# lights_node.net
KiCad netlist of a schematic drawn in EAGLE
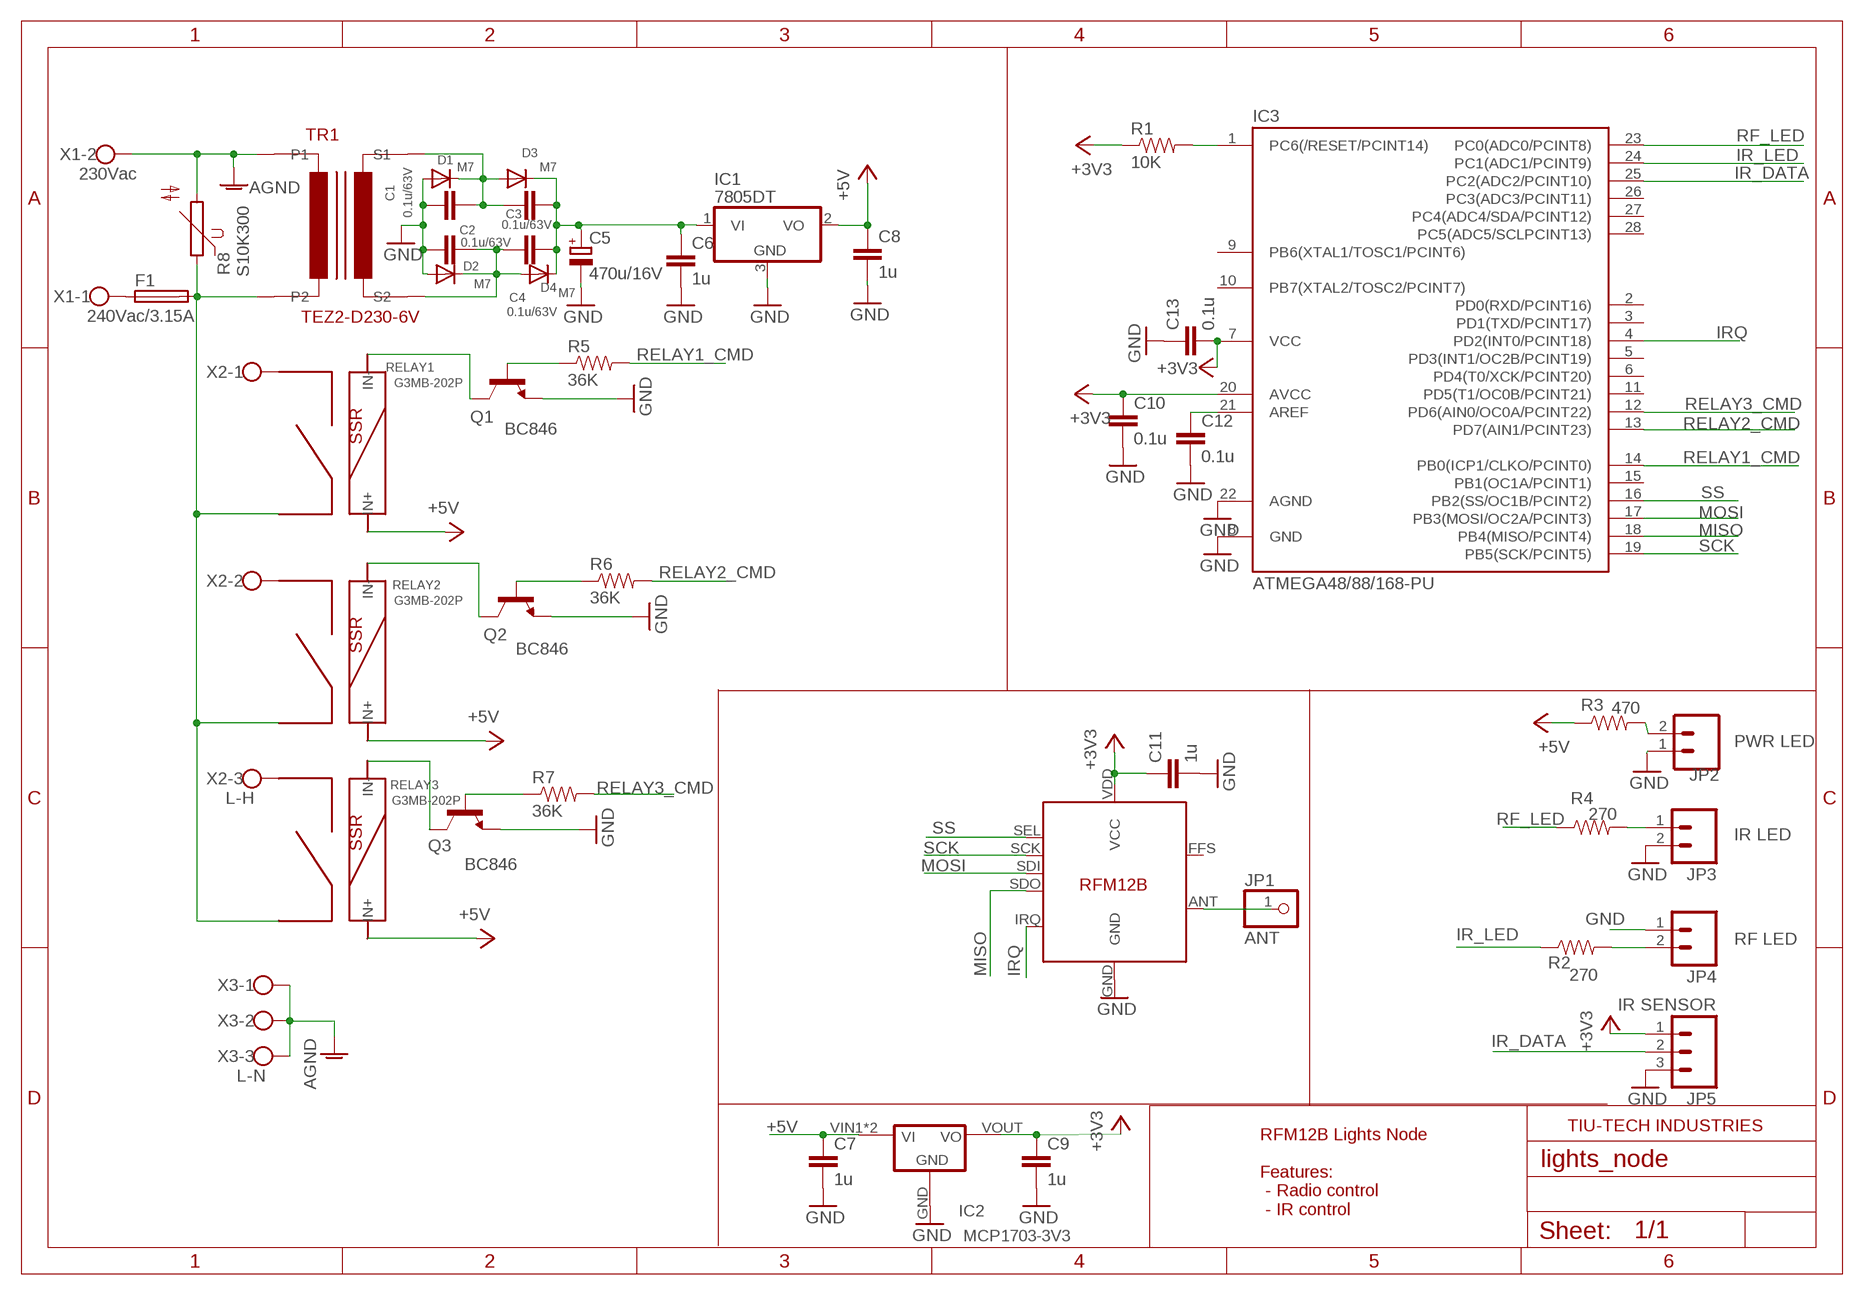
[diagram p0: schematic, sheet 1]

(export (version "E")
  (design (tool "Eeschema 10.0.6"))
  (components
    (comp (ref "C1")
      (value "0.1u/63V")
      (footprint "eagle-import:0805")
      (libsource (lib "eagle-import") (part "CAP0805"))
    )
    (comp (ref "C2")
      (value "0.1u/63V")
      (footprint "eagle-import:0805")
      (libsource (lib "eagle-import") (part "CAP0805"))
    )
    (comp (ref "C3")
      (value "0.1u/63V")
      (footprint "eagle-import:0805")
      (libsource (lib "eagle-import") (part "CAP0805"))
    )
    (comp (ref "C4")
      (value "0.1u/63V")
      (footprint "eagle-import:0805")
      (libsource (lib "eagle-import") (part "CAP0805"))
    )
    (comp (ref "C5")
      (value "470u/16V")
      (footprint "eagle-import:E2,5-7")
      (libsource (lib "eagle-import") (part "CPOL-EUE2.5-7"))
    )
    (comp (ref "C6")
      (value "1u")
      (footprint "eagle-import:0805")
      (libsource (lib "eagle-import") (part "CAP0805"))
    )
    (comp (ref "C7")
      (value "1u")
      (footprint "eagle-import:0805")
      (libsource (lib "eagle-import") (part "CAP0805"))
    )
    (comp (ref "C8")
      (value "1u")
      (footprint "eagle-import:0805")
      (libsource (lib "eagle-import") (part "CAP0805"))
    )
    (comp (ref "C9")
      (value "1u")
      (footprint "eagle-import:0805")
      (libsource (lib "eagle-import") (part "CAP0805"))
    )
    (comp (ref "C10")
      (value "0.1u")
      (footprint "eagle-import:0805")
      (libsource (lib "eagle-import") (part "CAP0805"))
    )
    (comp (ref "C11")
      (value "1u")
      (footprint "eagle-import:0805")
      (libsource (lib "eagle-import") (part "CAP0805"))
    )
    (comp (ref "C12")
      (value "0.1u")
      (footprint "eagle-import:0805")
      (libsource (lib "eagle-import") (part "CAP0805"))
    )
    (comp (ref "C13")
      (value "0.1u")
      (footprint "eagle-import:0805")
      (libsource (lib "eagle-import") (part "CAP0805"))
    )
    (comp (ref "D1")
      (value "M7")
      (footprint "eagle-import:DO-214AC")
      (libsource (lib "eagle-import") (part "DIODE-DO-214AC"))
    )
    (comp (ref "D2")
      (value "M7")
      (footprint "eagle-import:DO-214AC")
      (libsource (lib "eagle-import") (part "DIODE-DO-214AC"))
    )
    (comp (ref "D3")
      (value "M7")
      (footprint "eagle-import:DO-214AC")
      (libsource (lib "eagle-import") (part "DIODE-DO-214AC"))
    )
    (comp (ref "D4")
      (value "M7")
      (footprint "eagle-import:DO-214AC")
      (libsource (lib "eagle-import") (part "DIODE-DO-214AC"))
    )
    (comp (ref "F1")
      (value "240Vac/3.15A")
      (footprint "eagle-import:PICOFUSE")
      (libsource (lib "eagle-import") (part "PICOFUSE"))
    )
    (comp (ref "IC1")
      (value "7805DT")
      (footprint "eagle-import:TO252")
      (libsource (lib "eagle-import") (part "78DT05"))
    )
    (comp (ref "IC2")
      (value "MCP1703-3V3")
      (footprint "eagle-import:MCP1703-SOT89")
      (libsource (lib "eagle-import") (part "MCP1703-SOT89"))
    )
    (comp (ref "IC3")
      (value "ATMEGA48/88/168-PU")
      (footprint "eagle-import:DIL28-3")
      (libsource (lib "eagle-import") (part "ATMEGA48/88/168-PU"))
    )
    (comp (ref "JP1")
      (value "ANT")
      (footprint "eagle-import:1X01")
      (libsource (lib "eagle-import") (part "PINHD-1X1"))
    )
    (comp (ref "JP2")
      (value "M02PTH")
      (footprint "eagle-import:1X02")
      (libsource (lib "eagle-import") (part "M02PTH"))
    )
    (comp (ref "JP3")
      (value "M02PTH")
      (footprint "eagle-import:1X02")
      (libsource (lib "eagle-import") (part "M02PTH"))
    )
    (comp (ref "JP4")
      (value "M02PTH")
      (footprint "eagle-import:1X02")
      (libsource (lib "eagle-import") (part "M02PTH"))
    )
    (comp (ref "JP5")
      (value "IR SENSOR")
      (footprint "eagle-import:1X03")
      (libsource (lib "eagle-import") (part "M03PTH"))
    )
    (comp (ref "Q1")
      (value "BC846")
      (footprint "eagle-import:SOT23-BEC")
      (libsource (lib "eagle-import") (part "-NPN-SOT23-BECBC847C"))
    )
    (comp (ref "Q2")
      (value "BC846")
      (footprint "eagle-import:SOT23-BEC")
      (libsource (lib "eagle-import") (part "-NPN-SOT23-BECBC847C"))
    )
    (comp (ref "Q3")
      (value "BC846")
      (footprint "eagle-import:SOT23-BEC")
      (libsource (lib "eagle-import") (part "-NPN-SOT23-BECBC847C"))
    )
    (comp (ref "R1")
      (value "10K")
      (footprint "eagle-import:0805")
      (libsource (lib "eagle-import") (part "RESISTOR0805-RES"))
    )
    (comp (ref "R2")
      (value "270")
      (footprint "eagle-import:0805")
      (libsource (lib "eagle-import") (part "RESISTOR0805-RES"))
    )
    (comp (ref "R3")
      (value "470")
      (footprint "eagle-import:0805")
      (libsource (lib "eagle-import") (part "RESISTOR0805-RES"))
    )
    (comp (ref "R4")
      (value "270")
      (footprint "eagle-import:0805")
      (libsource (lib "eagle-import") (part "RESISTOR0805-RES"))
    )
    (comp (ref "R5")
      (value "36K")
      (footprint "eagle-import:0805")
      (libsource (lib "eagle-import") (part "SparkFun-Resistors_RESISTOR0805-RES"))
    )
    (comp (ref "R6")
      (value "36K")
      (footprint "eagle-import:0805")
      (libsource (lib "eagle-import") (part "SparkFun-Resistors_RESISTOR0805-RES"))
    )
    (comp (ref "R7")
      (value "36K")
      (footprint "eagle-import:0805")
      (libsource (lib "eagle-import") (part "SparkFun-Resistors_RESISTOR0805-RES"))
    )
    (comp (ref "R8")
      (value "S10K300")
      (footprint "eagle-import:S10K300")
      (libsource (lib "eagle-import") (part "S10K300"))
    )
    (comp (ref "RELAY1")
      (value "G3MB-202P")
      (footprint "eagle-import:G3MB-202P")
      (libsource (lib "eagle-import") (part "G3MB-202P"))
    )
    (comp (ref "RELAY2")
      (value "G3MB-202P")
      (footprint "eagle-import:G3MB-202P")
      (libsource (lib "eagle-import") (part "G3MB-202P"))
    )
    (comp (ref "RELAY3")
      (value "G3MB-202P")
      (footprint "eagle-import:G3MB-202P")
      (libsource (lib "eagle-import") (part "G3MB-202P"))
    )
    (comp (ref "RFM1")
      (value "RFM12B")
      (footprint "eagle-import:RFM12B")
      (libsource (lib "eagle-import") (part "RFM12B"))
    )
    (comp (ref "TR1")
      (value "TEZ2-D230-6V")
      (footprint "eagle-import:TEZ1.5-PKG")
      (libsource (lib "eagle-import") (part "TEZ1.5-D230-6V"))
    )
    (comp (ref "X1")
      (value "230Vac")
      (footprint "eagle-import:W237-102")
      (fields (field (name "MPN") "237-102"))
      (libsource (lib "eagle-import") (part "W237-102"))
    )
    (comp (ref "X2")
      (value "L-H")
      (footprint "eagle-import:W237-103")
      (fields (field (name "MPN") "237-103"))
      (libsource (lib "eagle-import") (part "W237-103"))
    )
    (comp (ref "X3")
      (value "L-N")
      (footprint "eagle-import:W237-103")
      (fields (field (name "MPN") "237-103"))
      (libsource (lib "eagle-import") (part "W237-103"))
    )
  )
  (nets
    (net (code "1") (name "+3V3") (class "Default")
      (node (ref "C10") (pin "1") (pinfunction "1_1") (pintype "passive"))
      (node (ref "C11") (pin "1") (pinfunction "1_1") (pintype "passive"))
      (node (ref "C13") (pin "2") (pinfunction "2_2") (pintype "passive"))
      (node (ref "C9") (pin "1") (pinfunction "1_1") (pintype "passive"))
      (node (ref "IC2") (pin "VOUT") (pinfunction "VO_VOUT") (pintype "passive"))
      (node (ref "IC3") (pin "20") (pinfunction "AVCC_20") (pintype "passive"))
      (node (ref "IC3") (pin "7") (pinfunction "VCC_7") (pintype "power_in"))
      (node (ref "JP5") (pin "1") (pinfunction "1_1") (pintype "passive"))
      (node (ref "R1") (pin "1") (pinfunction "1_1") (pintype "passive"))
      (node (ref "RFM1") (pin "VDD") (pinfunction "VCC_VDD") (pintype "power_in"))
    )
    (net (code "2") (name "+5V") (class "Default")
      (node (ref "C7") (pin "1") (pinfunction "1_1") (pintype "passive"))
      (node (ref "C8") (pin "1") (pinfunction "1_1") (pintype "passive"))
      (node (ref "IC1") (pin "2") (pinfunction "VO_2") (pintype "passive"))
      (node (ref "IC2") (pin "VIN1") (pinfunction "VI_VIN1") (pintype "power_in"))
      (node (ref "IC2") (pin "VIN2") (pinfunction "VI_VIN2") (pintype "power_in"))
      (node (ref "R3") (pin "1") (pinfunction "1_1") (pintype "passive"))
      (node (ref "RELAY1") (pin "IN+") (pinfunction "IN+_IN+") (pintype "bidirectional"))
      (node (ref "RELAY2") (pin "IN+") (pinfunction "IN+_IN+") (pintype "bidirectional"))
      (node (ref "RELAY3") (pin "IN+") (pinfunction "IN+_IN+") (pintype "bidirectional"))
    )
    (net (code "3") (name "/IRQ") (class "Default")
      (node (ref "IC3") (pin "4") (pinfunction "PD2(INT0/PCINT18)_4") (pintype "bidirectional"))
      (node (ref "RFM1") (pin "IRQ") (pinfunction "IRQ_IRQ") (pintype "open_collector"))
    )
    (net (code "4") (name "/IR_DATA") (class "Default")
      (node (ref "IC3") (pin "25") (pinfunction "PC2(ADC2/PCINT10)_25") (pintype "bidirectional"))
      (node (ref "JP5") (pin "2") (pinfunction "2_2") (pintype "passive"))
    )
    (net (code "5") (name "/IR_LED") (class "Default")
      (node (ref "IC3") (pin "24") (pinfunction "PC1(ADC1/PCINT9)_24") (pintype "bidirectional"))
      (node (ref "R2") (pin "1") (pinfunction "1_1") (pintype "passive"))
    )
    (net (code "6") (name "/MISO") (class "Default")
      (node (ref "IC3") (pin "18") (pinfunction "PB4(MISO/PCINT4)_18") (pintype "bidirectional"))
      (node (ref "RFM1") (pin "SDO") (pinfunction "SDO_SDO") (pintype "output"))
    )
    (net (code "7") (name "/MOSI") (class "Default")
      (node (ref "IC3") (pin "17") (pinfunction "PB3(MOSI/OC2A/PCINT3)_17") (pintype "bidirectional"))
      (node (ref "RFM1") (pin "SDI") (pinfunction "SDI_SDI") (pintype "input"))
    )
    (net (code "8") (name "/RELAY1_CMD") (class "Default")
      (node (ref "IC3") (pin "14") (pinfunction "PB0(ICP1/CLKO/PCINT0)_14") (pintype "bidirectional"))
      (node (ref "R5") (pin "2") (pinfunction "2_2") (pintype "passive"))
    )
    (net (code "9") (name "/RELAY2_CMD") (class "Default")
      (node (ref "IC3") (pin "13") (pinfunction "PD7(AIN1/PCINT23)_13") (pintype "bidirectional"))
      (node (ref "R6") (pin "2") (pinfunction "2_2") (pintype "passive"))
    )
    (net (code "10") (name "/RELAY3_CMD") (class "Default")
      (node (ref "IC3") (pin "12") (pinfunction "PD6(AIN0/OC0A/PCINT22)_12") (pintype "bidirectional"))
      (node (ref "R7") (pin "2") (pinfunction "2_2") (pintype "passive"))
    )
    (net (code "11") (name "/RF_LED") (class "Default")
      (node (ref "IC3") (pin "23") (pinfunction "PC0(ADC0/PCINT8)_23") (pintype "bidirectional"))
      (node (ref "R4") (pin "1") (pinfunction "1_1") (pintype "passive"))
    )
    (net (code "12") (name "/SCK") (class "Default")
      (node (ref "IC3") (pin "19") (pinfunction "PB5(SCK/PCINT5)_19") (pintype "bidirectional"))
      (node (ref "RFM1") (pin "SCK") (pinfunction "SCK_SCK") (pintype "input"))
    )
    (net (code "13") (name "/SS") (class "Default")
      (node (ref "IC3") (pin "16") (pinfunction "PB2(SS/OC1B/PCINT2)_16") (pintype "bidirectional"))
      (node (ref "RFM1") (pin "SEL") (pinfunction "SEL_SEL") (pintype "input"))
    )
    (net (code "14") (name "AGND") (class "Default")
      (node (ref "R8") (pin "2") (pinfunction "2_2") (pintype "passive"))
      (node (ref "TR1") (pin "P1") (pinfunction "P1_P1") (pintype "bidirectional"))
      (node (ref "X1") (pin "2") (pinfunction "KL_2") (pintype "passive"))
      (node (ref "X3") (pin "1") (pinfunction "KL_1") (pintype "passive"))
      (node (ref "X3") (pin "2") (pinfunction "KL_2") (pintype "passive"))
      (node (ref "X3") (pin "3") (pinfunction "KL_3") (pintype "passive"))
    )
    (net (code "15") (name "GND") (class "Default")
      (node (ref "C1") (pin "1") (pinfunction "1_1") (pintype "passive"))
      (node (ref "C10") (pin "2") (pinfunction "2_2") (pintype "passive"))
      (node (ref "C11") (pin "2") (pinfunction "2_2") (pintype "passive"))
      (node (ref "C12") (pin "2") (pinfunction "2_2") (pintype "passive"))
      (node (ref "C13") (pin "1") (pinfunction "1_1") (pintype "passive"))
      (node (ref "C2") (pin "1") (pinfunction "1_1") (pintype "passive"))
      (node (ref "C5") (pin "-") (pinfunction "-_-") (pintype "passive"))
      (node (ref "C6") (pin "2") (pinfunction "2_2") (pintype "passive"))
      (node (ref "C7") (pin "2") (pinfunction "2_2") (pintype "passive"))
      (node (ref "C8") (pin "2") (pinfunction "2_2") (pintype "passive"))
      (node (ref "C9") (pin "2") (pinfunction "2_2") (pintype "passive"))
      (node (ref "D1") (pin "A") (pinfunction "A_A") (pintype "passive"))
      (node (ref "D2") (pin "A") (pinfunction "A_A") (pintype "passive"))
      (node (ref "IC1") (pin "3") (pinfunction "GND_3") (pintype "passive"))
      (node (ref "IC2") (pin "GND") (pinfunction "GND_GND") (pintype "power_in"))
      (node (ref "IC3") (pin "22") (pinfunction "AGND_22") (pintype "power_in"))
      (node (ref "IC3") (pin "8") (pinfunction "GND_8") (pintype "power_in"))
      (node (ref "JP2") (pin "1") (pinfunction "1_1") (pintype "passive"))
      (node (ref "JP3") (pin "2") (pinfunction "2_2") (pintype "passive"))
      (node (ref "JP4") (pin "1") (pinfunction "1_1") (pintype "passive"))
      (node (ref "JP5") (pin "3") (pinfunction "3_3") (pintype "passive"))
      (node (ref "Q1") (pin "E") (pinfunction "E_E") (pintype "passive"))
      (node (ref "Q2") (pin "E") (pinfunction "E_E") (pintype "passive"))
      (node (ref "Q3") (pin "E") (pinfunction "E_E") (pintype "passive"))
      (node (ref "RFM1") (pin "GND") (pinfunction "GND_GND") (pintype "power_in"))
    )
    (net (code "16") (name "Net-(IC1-VI)") (class "Default")
      (node (ref "C3") (pin "2") (pinfunction "2_2") (pintype "passive"))
      (node (ref "C4") (pin "2") (pinfunction "2_2") (pintype "passive"))
      (node (ref "C5") (pin "+") (pinfunction "+_+") (pintype "passive"))
      (node (ref "C6") (pin "1") (pinfunction "1_1") (pintype "passive"))
      (node (ref "D3") (pin "C") (pinfunction "C_C") (pintype "passive"))
      (node (ref "D4") (pin "C") (pinfunction "C_C") (pintype "passive"))
      (node (ref "IC1") (pin "1") (pinfunction "VI_1") (pintype "input"))
    )
    (net (code "17") (name "Net-(IC3-AREF)") (class "Default")
      (node (ref "C12") (pin "1") (pinfunction "1_1") (pintype "passive"))
      (node (ref "IC3") (pin "21") (pinfunction "AREF_21") (pintype "passive"))
    )
    (net (code "18") (name "Net-(IC3-PC6({slash}RESET{slash}PCINT14))") (class "Default")
      (node (ref "IC3") (pin "1") (pinfunction "PC6(/RESET/PCINT14)_1") (pintype "bidirectional"))
      (node (ref "R1") (pin "2") (pinfunction "2_2") (pintype "passive"))
    )
    (net (code "19") (name "Net-(JP1-Pad1)") (class "Default")
      (node (ref "JP1") (pin "1") (pinfunction "1_1") (pintype "passive"))
      (node (ref "RFM1") (pin "ANT") (pinfunction "ANT_ANT") (pintype "passive"))
    )
    (net (code "20") (name "Net-(JP2-Pad2)") (class "Default")
      (node (ref "JP2") (pin "2") (pinfunction "2_2") (pintype "passive"))
      (node (ref "R3") (pin "2") (pinfunction "2_2") (pintype "passive"))
    )
    (net (code "21") (name "Net-(JP3-Pad1)") (class "Default")
      (node (ref "JP3") (pin "1") (pinfunction "1_1") (pintype "passive"))
      (node (ref "R4") (pin "2") (pinfunction "2_2") (pintype "passive"))
    )
    (net (code "22") (name "Net-(JP4-Pad2)") (class "Default")
      (node (ref "JP4") (pin "2") (pinfunction "2_2") (pintype "passive"))
      (node (ref "R2") (pin "2") (pinfunction "2_2") (pintype "passive"))
    )
    (net (code "23") (name "Net-(Q1-PadB)") (class "Default")
      (node (ref "Q1") (pin "B") (pinfunction "B_B") (pintype "passive"))
      (node (ref "R5") (pin "1") (pinfunction "1_1") (pintype "passive"))
    )
    (net (code "24") (name "Net-(Q1-PadC)") (class "Default")
      (node (ref "Q1") (pin "C") (pinfunction "C_C") (pintype "passive"))
      (node (ref "RELAY1") (pin "IN-") (pinfunction "IN-_IN-") (pintype "bidirectional"))
    )
    (net (code "25") (name "Net-(Q2-PadB)") (class "Default")
      (node (ref "Q2") (pin "B") (pinfunction "B_B") (pintype "passive"))
      (node (ref "R6") (pin "1") (pinfunction "1_1") (pintype "passive"))
    )
    (net (code "26") (name "Net-(Q2-PadC)") (class "Default")
      (node (ref "Q2") (pin "C") (pinfunction "C_C") (pintype "passive"))
      (node (ref "RELAY2") (pin "IN-") (pinfunction "IN-_IN-") (pintype "bidirectional"))
    )
    (net (code "27") (name "Net-(Q3-PadB)") (class "Default")
      (node (ref "Q3") (pin "B") (pinfunction "B_B") (pintype "passive"))
      (node (ref "R7") (pin "1") (pinfunction "1_1") (pintype "passive"))
    )
    (net (code "28") (name "Net-(Q3-PadC)") (class "Default")
      (node (ref "Q3") (pin "C") (pinfunction "C_C") (pintype "passive"))
      (node (ref "RELAY3") (pin "IN-") (pinfunction "IN-_IN-") (pintype "bidirectional"))
    )
    (net (code "29") (name "Net-(TR1-P2)") (class "Default")
      (node (ref "F1") (pin "2") (pinfunction "2_2") (pintype "passive"))
      (node (ref "R8") (pin "1") (pinfunction "1_1") (pintype "passive"))
      (node (ref "RELAY1") (pin "K1") (pinfunction "K1_K1") (pintype "bidirectional"))
      (node (ref "RELAY2") (pin "K1") (pinfunction "K1_K1") (pintype "bidirectional"))
      (node (ref "RELAY3") (pin "K1") (pinfunction "K1_K1") (pintype "bidirectional"))
      (node (ref "TR1") (pin "P5") (pinfunction "P2_P5") (pintype "bidirectional"))
    )
    (net (code "30") (name "Net-(TR1-S1)") (class "Default")
      (node (ref "C1") (pin "2") (pinfunction "2_2") (pintype "passive"))
      (node (ref "C3") (pin "1") (pinfunction "1_1") (pintype "passive"))
      (node (ref "D1") (pin "C") (pinfunction "C_C") (pintype "passive"))
      (node (ref "D3") (pin "A") (pinfunction "A_A") (pintype "passive"))
      (node (ref "TR1") (pin "S7") (pinfunction "S1_S7") (pintype "bidirectional"))
    )
    (net (code "31") (name "Net-(TR1-S2)") (class "Default")
      (node (ref "C2") (pin "2") (pinfunction "2_2") (pintype "passive"))
      (node (ref "C4") (pin "1") (pinfunction "1_1") (pintype "passive"))
      (node (ref "D2") (pin "C") (pinfunction "C_C") (pintype "passive"))
      (node (ref "D4") (pin "A") (pinfunction "A_A") (pintype "passive"))
      (node (ref "TR1") (pin "S9") (pinfunction "S2_S9") (pintype "bidirectional"))
    )
    (net (code "32") (name "Net-(X1A-KL)") (class "Default")
      (node (ref "F1") (pin "1") (pinfunction "1_1") (pintype "passive"))
      (node (ref "X1") (pin "1") (pinfunction "KL_1") (pintype "passive"))
    )
    (net (code "33") (name "Net-(X2A-KL)") (class "Default")
      (node (ref "RELAY1") (pin "K2") (pinfunction "K2_K2") (pintype "bidirectional"))
      (node (ref "X2") (pin "1") (pinfunction "KL_1") (pintype "passive"))
    )
    (net (code "34") (name "Net-(X2B-KL)") (class "Default")
      (node (ref "RELAY2") (pin "K2") (pinfunction "K2_K2") (pintype "bidirectional"))
      (node (ref "X2") (pin "2") (pinfunction "KL_2") (pintype "passive"))
    )
    (net (code "35") (name "Net-(X2C-KL)") (class "Default")
      (node (ref "RELAY3") (pin "K2") (pinfunction "K2_K2") (pintype "bidirectional"))
      (node (ref "X2") (pin "3") (pinfunction "KL_3") (pintype "passive"))
    )
    (net (code "36") (name "unconnected-(IC3-PB1(OC1A{slash}PCINT1)-Pad15)") (class "Default")
      (node (ref "IC3") (pin "15") (pinfunction "PB1(OC1A/PCINT1)_15") (pintype "bidirectional"))
    )
    (net (code "37") (name "unconnected-(IC3-PB6(XTAL1{slash}TOSC1{slash}PCINT6)-Pad9)") (class "Default")
      (node (ref "IC3") (pin "9") (pinfunction "PB6(XTAL1/TOSC1/PCINT6)_9") (pintype "bidirectional"))
    )
    (net (code "38") (name "unconnected-(IC3-PB7(XTAL2{slash}TOSC2{slash}PCINT7)-Pad10)") (class "Default")
      (node (ref "IC3") (pin "10") (pinfunction "PB7(XTAL2/TOSC2/PCINT7)_10") (pintype "bidirectional"))
    )
    (net (code "39") (name "unconnected-(IC3-PC3(ADC3{slash}PCINT11)-Pad26)") (class "Default")
      (node (ref "IC3") (pin "26") (pinfunction "PC3(ADC3/PCINT11)_26") (pintype "bidirectional"))
    )
    (net (code "40") (name "unconnected-(IC3-PC4(ADC4{slash}SDA{slash}PCINT12)-Pad27)") (class "Default")
      (node (ref "IC3") (pin "27") (pinfunction "PC4(ADC4/SDA/PCINT12)_27") (pintype "bidirectional"))
    )
    (net (code "41") (name "unconnected-(IC3-PC5(ADC5{slash}SCLPCINT13)-Pad28)") (class "Default")
      (node (ref "IC3") (pin "28") (pinfunction "PC5(ADC5/SCLPCINT13)_28") (pintype "bidirectional"))
    )
    (net (code "42") (name "unconnected-(IC3-PD0(RXD{slash}PCINT16)-Pad2)") (class "Default")
      (node (ref "IC3") (pin "2") (pinfunction "PD0(RXD/PCINT16)_2") (pintype "bidirectional"))
    )
    (net (code "43") (name "unconnected-(IC3-PD1(TXD{slash}PCINT17)-Pad3)") (class "Default")
      (node (ref "IC3") (pin "3") (pinfunction "PD1(TXD/PCINT17)_3") (pintype "bidirectional"))
    )
    (net (code "44") (name "unconnected-(IC3-PD3(INT1{slash}OC2B{slash}PCINT19)-Pad5)") (class "Default")
      (node (ref "IC3") (pin "5") (pinfunction "PD3(INT1/OC2B/PCINT19)_5") (pintype "bidirectional"))
    )
    (net (code "45") (name "unconnected-(IC3-PD4(T0{slash}XCK{slash}PCINT20)-Pad6)") (class "Default")
      (node (ref "IC3") (pin "6") (pinfunction "PD4(T0/XCK/PCINT20)_6") (pintype "bidirectional"))
    )
    (net (code "46") (name "unconnected-(IC3-PD5(T1{slash}OC0B{slash}PCINT21)-Pad11)") (class "Default")
      (node (ref "IC3") (pin "11") (pinfunction "PD5(T1/OC0B/PCINT21)_11") (pintype "bidirectional"))
    )
    (net (code "47") (name "unconnected-(RFM1-PadFFS)") (class "Default")
      (node (ref "RFM1") (pin "FFS") (pinfunction "FFS_FFS") (pintype "bidirectional"))
    )
  )
)
